# XMOD_Thermal.net
KiCad netlist of a schematic drawn in Altium Designer
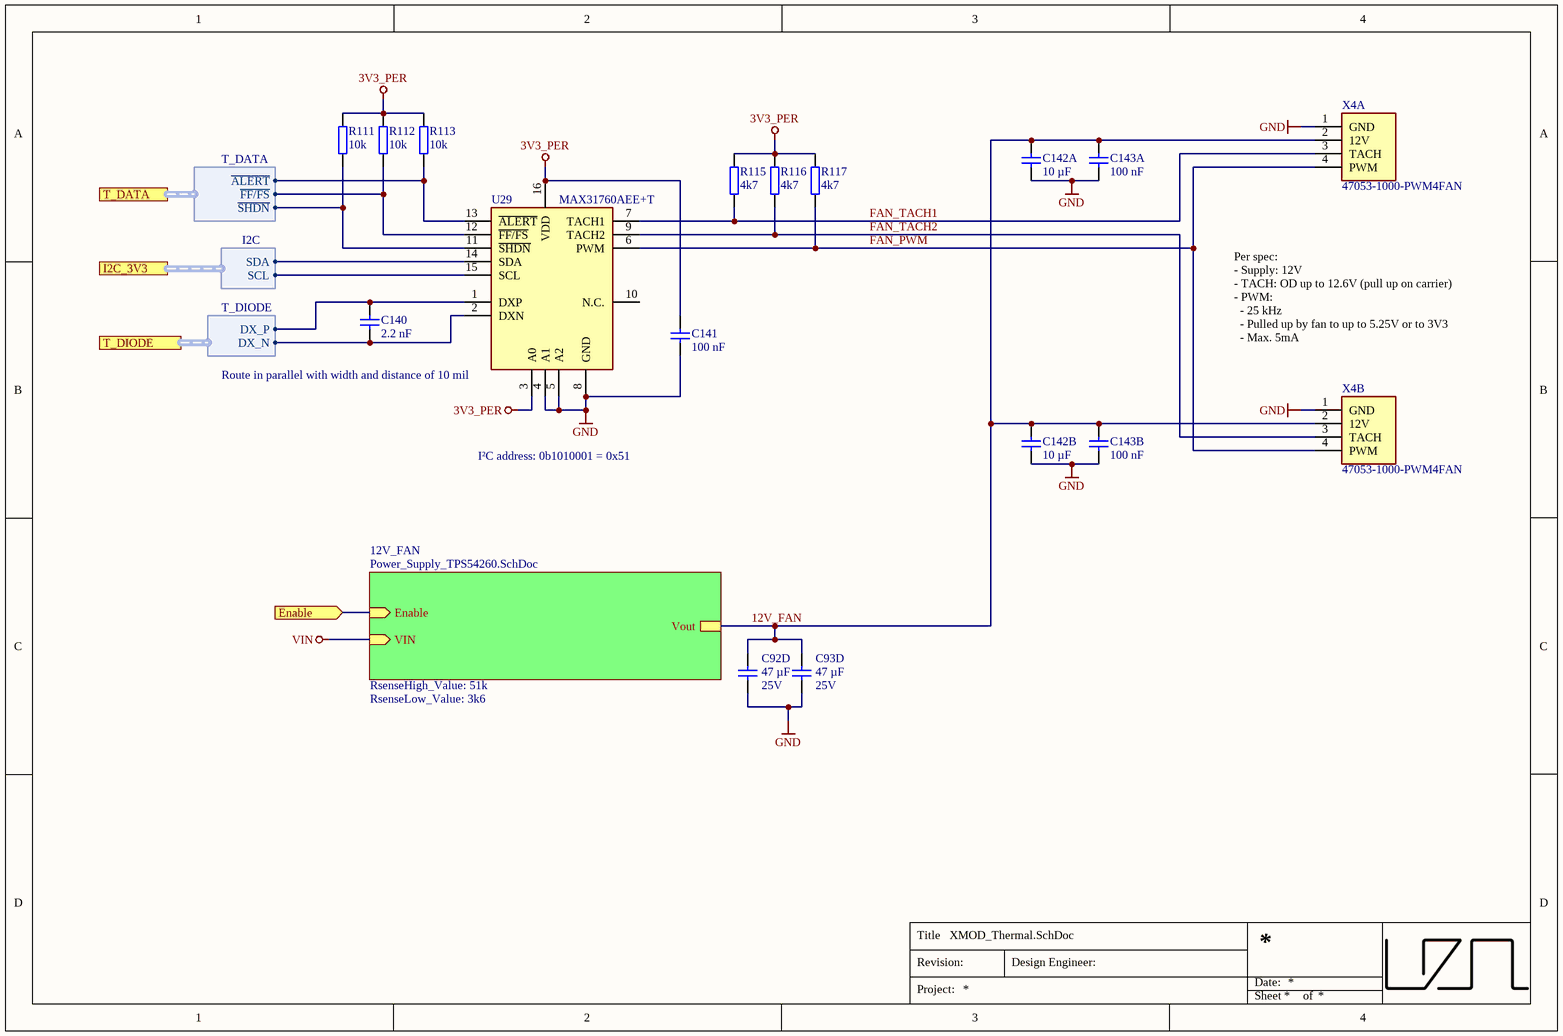
[diagram p0: XMOD_Thermal.SchDoc]

(export (version "E")
  (design (tool "Eeschema 10.0.6"))
  (components
    (comp (ref "C92D")
      (value "47 µF")
      (footprint "C_1206_TE")
      (description "Generic capacitor")
      (fields
        (field (name "TOLERANCE") "10 %")
        (field (name "VOLTAGE") "25V")
        (field (name "MANUFACTURER PART NUMBER") "UZgen_C_1206_47uF_25V_X7R")
        (field (name "CREATED FROM") "UZgenTool")
      )
      (libsource (lib "user") (part "CAP-NP"))
    )
    (comp (ref "C93D")
      (value "47 µF")
      (footprint "C_1206_TE")
      (description "Generic capacitor")
      (fields
        (field (name "TOLERANCE") "10 %")
        (field (name "VOLTAGE") "25V")
        (field (name "MANUFACTURER PART NUMBER") "UZgen_C_1206_47uF_25V_X7R")
        (field (name "CREATED FROM") "UZgenTool")
      )
      (libsource (lib "user") (part "CAP-NP"))
    )
    (comp (ref "C140")
      (value "2.2 nF")
      (footprint "C_0603_TE")
      (description "Generic capacitor")
      (fields
        (field (name "MANUFACTURER PART NUMBER") "UZgen_C_0603_2.2nF_50V_X7R")
        (field (name "MANUFACTURER") "UZgen")
        (field (name "CREATED FROM") "UZgenTool")
      )
      (libsource (lib "user") (part "CAP-NP"))
    )
    (comp (ref "C141")
      (value "100 nF")
      (footprint "C_0603_TE")
      (description "Generic capacitor")
      (fields
        (field (name "MANUFACTURER PART NUMBER") "UZgen_C_0603_100nF_50V_X7R")
        (field (name "MANUFACTURER") "UZgen")
        (field (name "CREATED FROM") "AGeiger")
      )
      (libsource (lib "user") (part "CAP-NP"))
    )
    (comp (ref "C142A")
      (value "10 µF")
      (footprint "C_1206_TE")
      (description "50V 10uF X7R ±10% 1206  Multilayer Ceramic Capacitors MLCC - SMD/SMT ROHS")
      (fields
        (field (name "MANUFACTURER PART NUMBER") "CL31B106KBHNNNE")
        (field (name "MANUFACTURER") "Samsung Electro-Mechanics")
        (field (name "CREATED FROM") "AGeiger")
      )
      (libsource (lib "user") (part "CAP-NP"))
    )
    (comp (ref "C142B")
      (value "10 µF")
      (footprint "C_1206_TE")
      (description "50V 10uF X7R ±10% 1206  Multilayer Ceramic Capacitors MLCC - SMD/SMT ROHS")
      (fields
        (field (name "MANUFACTURER PART NUMBER") "CL31B106KBHNNNE")
        (field (name "MANUFACTURER") "Samsung Electro-Mechanics")
        (field (name "CREATED FROM") "AGeiger")
      )
      (libsource (lib "user") (part "CAP-NP"))
    )
    (comp (ref "C143A")
      (value "100 nF")
      (footprint "C_0603_TE")
      (description "Generic capacitor")
      (fields
        (field (name "MANUFACTURER PART NUMBER") "UZgen_C_0603_100nF_50V_X7R")
        (field (name "MANUFACTURER") "UZgen")
        (field (name "CREATED FROM") "AGeiger")
      )
      (libsource (lib "user") (part "CAP-NP"))
    )
    (comp (ref "C143B")
      (value "100 nF")
      (footprint "C_0603_TE")
      (description "Generic capacitor")
      (fields
        (field (name "MANUFACTURER PART NUMBER") "UZgen_C_0603_100nF_50V_X7R")
        (field (name "MANUFACTURER") "UZgen")
        (field (name "CREATED FROM") "AGeiger")
      )
      (libsource (lib "user") (part "CAP-NP"))
    )
    (comp (ref "R111")
      (value "10k")
      (footprint "R_0603_TE")
      (description "Generic resistor")
      (fields
        (field (name "MANUFACTURER PART NUMBER") "UZgen_R_0603_10k")
        (field (name "MANUFACTURER") "UZgen")
        (field (name "CREATED FROM") "AGeiger")
      )
      (libsource (lib "user") (part "RES"))
    )
    (comp (ref "R112")
      (value "10k")
      (footprint "R_0603_TE")
      (description "Generic resistor")
      (fields
        (field (name "MANUFACTURER PART NUMBER") "UZgen_R_0603_10k")
        (field (name "MANUFACTURER") "UZgen")
        (field (name "CREATED FROM") "AGeiger")
      )
      (libsource (lib "user") (part "RES"))
    )
    (comp (ref "R113")
      (value "10k")
      (footprint "R_0603_TE")
      (description "Generic resistor")
      (fields
        (field (name "MANUFACTURER PART NUMBER") "UZgen_R_0603_10k")
        (field (name "MANUFACTURER") "UZgen")
        (field (name "CREATED FROM") "AGeiger")
      )
      (libsource (lib "user") (part "RES"))
    )
    (comp (ref "R115")
      (value "4k7")
      (footprint "R_0603_TE")
      (description "Generic resistor")
      (fields
        (field (name "MANUFACTURER PART NUMBER") "UZgen_R_0603_4k7")
        (field (name "MANUFACTURER") "UZgen")
        (field (name "CREATED FROM") "UZgenTool")
      )
      (libsource (lib "user") (part "RES"))
    )
    (comp (ref "R116")
      (value "4k7")
      (footprint "R_0603_TE")
      (description "Generic resistor")
      (fields
        (field (name "MANUFACTURER PART NUMBER") "UZgen_R_0603_4k7")
        (field (name "MANUFACTURER") "UZgen")
        (field (name "CREATED FROM") "UZgenTool")
      )
      (libsource (lib "user") (part "RES"))
    )
    (comp (ref "R117")
      (value "4k7")
      (footprint "R_0603_TE")
      (description "Generic resistor")
      (fields
        (field (name "MANUFACTURER PART NUMBER") "UZgen_R_0603_4k7")
        (field (name "MANUFACTURER") "UZgen")
        (field (name "CREATED FROM") "UZgenTool")
      )
      (libsource (lib "user") (part "RES"))
    )
    (comp (ref "U29")
      (value "MAX31760AEE+T")
      (footprint "SOP64P602X175-16N")
      (description "Motor/Motion/Ignition Controllers & Drivers Fan Speed Controller with LUT t&r")
      (fields
        (field (name "MANUFACTURER") "Analog Devices Inc.")
        (field (name "LCSC PART NUMBER") "C3031567")
        (field (name "CREATED FROM") "FRosner")
      )
      (libsource (lib "user") (part "MAX31760AEE+"))
    )
    (comp (ref "X4A")
      (value "47053-1000-PWM4FAN")
      (footprint "470531000")
      (description "Headers & Wire Housings 4P VERT HDR W/FL")
      (fields
        (field (name "MANUFACTURER_PART_NUMBER") "47053-1000")
        (field (name "MOUSER PART NUMBER") "538-47053-1000")
        (field (name "CREATED FROM") "FRosner")
      )
      (libsource (lib "user") (part "470531000-PWM4FAN"))
    )
    (comp (ref "X4B")
      (value "47053-1000-PWM4FAN")
      (footprint "470531000")
      (description "Headers & Wire Housings 4P VERT HDR W/FL")
      (fields
        (field (name "MANUFACTURER_PART_NUMBER") "47053-1000")
        (field (name "MOUSER PART NUMBER") "538-47053-1000")
        (field (name "CREATED FROM") "FRosner")
      )
      (libsource (lib "user") (part "470531000-PWM4FAN"))
    )
  )
  (nets
    (net (code "4") (name "/12V_FAN") (class "Default")
      (node (ref "C142A") (pin "2") (pinfunction "2_2") (pintype "passive"))
      (node (ref "C142B") (pin "2") (pinfunction "2_2") (pintype "passive"))
      (node (ref "C143A") (pin "2") (pinfunction "2_2") (pintype "passive"))
      (node (ref "C143B") (pin "2") (pinfunction "2_2") (pintype "passive"))
      (node (ref "C92D") (pin "2") (pinfunction "2_2") (pintype "passive"))
      (node (ref "C93D") (pin "2") (pinfunction "2_2") (pintype "passive"))
      (node (ref "X4A") (pin "2") (pinfunction "12V_2") (pintype "passive"))
      (node (ref "X4B") (pin "2") (pinfunction "12V_2") (pintype "passive"))
    )
    (net (code "5") (name "/DX_N") (class "Default")
      (node (ref "C140") (pin "1") (pinfunction "1_1") (pintype "passive"))
      (node (ref "U29") (pin "2") (pinfunction "DXN_2") (pintype "passive"))
    )
    (net (code "6") (name "/DX_P") (class "Default")
      (node (ref "C140") (pin "2") (pinfunction "2_2") (pintype "passive"))
      (node (ref "U29") (pin "1") (pinfunction "DXP_1") (pintype "passive"))
    )
    (net (code "8") (name "/FAN_PWM") (class "Default")
      (node (ref "R117") (pin "1") (pinfunction "1_1") (pintype "passive"))
      (node (ref "U29") (pin "6") (pinfunction "PWM_6") (pintype "passive"))
      (node (ref "X4A") (pin "4") (pinfunction "PWM_4") (pintype "passive"))
      (node (ref "X4B") (pin "4") (pinfunction "PWM_4") (pintype "passive"))
    )
    (net (code "9") (name "/FAN_TACH1") (class "Default")
      (node (ref "R115") (pin "1") (pinfunction "1_1") (pintype "passive"))
      (node (ref "U29") (pin "7") (pinfunction "TACH1_7") (pintype "passive"))
      (node (ref "X4A") (pin "3") (pinfunction "TACH_3") (pintype "passive"))
    )
    (net (code "10") (name "/FAN_TACH2") (class "Default")
      (node (ref "R116") (pin "1") (pinfunction "1_1") (pintype "passive"))
      (node (ref "U29") (pin "9") (pinfunction "TACH2_9") (pintype "passive"))
      (node (ref "X4B") (pin "3") (pinfunction "TACH_3") (pintype "passive"))
    )
    (net (code "11") (name "/SCL") (class "Default")
      (node (ref "U29") (pin "15") (pinfunction "SCL_15") (pintype "passive"))
    )
    (net (code "12") (name "/SDA") (class "Default")
      (node (ref "U29") (pin "14") (pinfunction "SDA_14") (pintype "passive"))
    )
    (net (code "16") (name "/~{ALERT}") (class "Default")
      (node (ref "R113") (pin "1") (pinfunction "1_1") (pintype "passive"))
      (node (ref "U29") (pin "13") (pinfunction "~{ALERT}_13") (pintype "passive"))
    )
    (net (code "17") (name "/~{FF{slash}FS}") (class "Default")
      (node (ref "R112") (pin "1") (pinfunction "1_1") (pintype "passive"))
      (node (ref "U29") (pin "12") (pinfunction "~{FF/FS}_12") (pintype "passive"))
    )
    (net (code "18") (name "/~{SHDN}") (class "Default")
      (node (ref "R111") (pin "1") (pinfunction "1_1") (pintype "passive"))
      (node (ref "U29") (pin "11") (pinfunction "~{SHDN}_11") (pintype "passive"))
    )
    (net (code "19") (name "3V3_PER") (class "Default")
      (node (ref "C141") (pin "2") (pinfunction "2_2") (pintype "passive"))
      (node (ref "R111") (pin "2") (pinfunction "2_2") (pintype "passive"))
      (node (ref "R112") (pin "2") (pinfunction "2_2") (pintype "passive"))
      (node (ref "R113") (pin "2") (pinfunction "2_2") (pintype "passive"))
      (node (ref "R115") (pin "2") (pinfunction "2_2") (pintype "passive"))
      (node (ref "R116") (pin "2") (pinfunction "2_2") (pintype "passive"))
      (node (ref "R117") (pin "2") (pinfunction "2_2") (pintype "passive"))
      (node (ref "U29") (pin "16") (pinfunction "VDD_16") (pintype "passive"))
      (node (ref "U29") (pin "3") (pinfunction "A0_3") (pintype "passive"))
    )
    (net (code "20") (name "GND") (class "Default")
      (node (ref "C141") (pin "1") (pinfunction "1_1") (pintype "passive"))
      (node (ref "C142A") (pin "1") (pinfunction "1_1") (pintype "passive"))
      (node (ref "C142B") (pin "1") (pinfunction "1_1") (pintype "passive"))
      (node (ref "C143A") (pin "1") (pinfunction "1_1") (pintype "passive"))
      (node (ref "C143B") (pin "1") (pinfunction "1_1") (pintype "passive"))
      (node (ref "C92D") (pin "1") (pinfunction "1_1") (pintype "passive"))
      (node (ref "C93D") (pin "1") (pinfunction "1_1") (pintype "passive"))
      (node (ref "U29") (pin "4") (pinfunction "A1_4") (pintype "passive"))
      (node (ref "U29") (pin "5") (pinfunction "A2_5") (pintype "passive"))
      (node (ref "U29") (pin "8") (pinfunction "GND_8") (pintype "passive"))
      (node (ref "X4A") (pin "1") (pinfunction "GND_1") (pintype "passive"))
      (node (ref "X4B") (pin "1") (pinfunction "GND_1") (pintype "passive"))
    )
    (net (code "22") (name "unconnected-(U29-N.C.-Pad10)") (class "Default")
      (node (ref "U29") (pin "10") (pinfunction "N.C._10") (pintype "passive"))
    )
  )
)
